# Drone_esp32-S3.net
KiCad netlist of a schematic drawn in Altium Designer
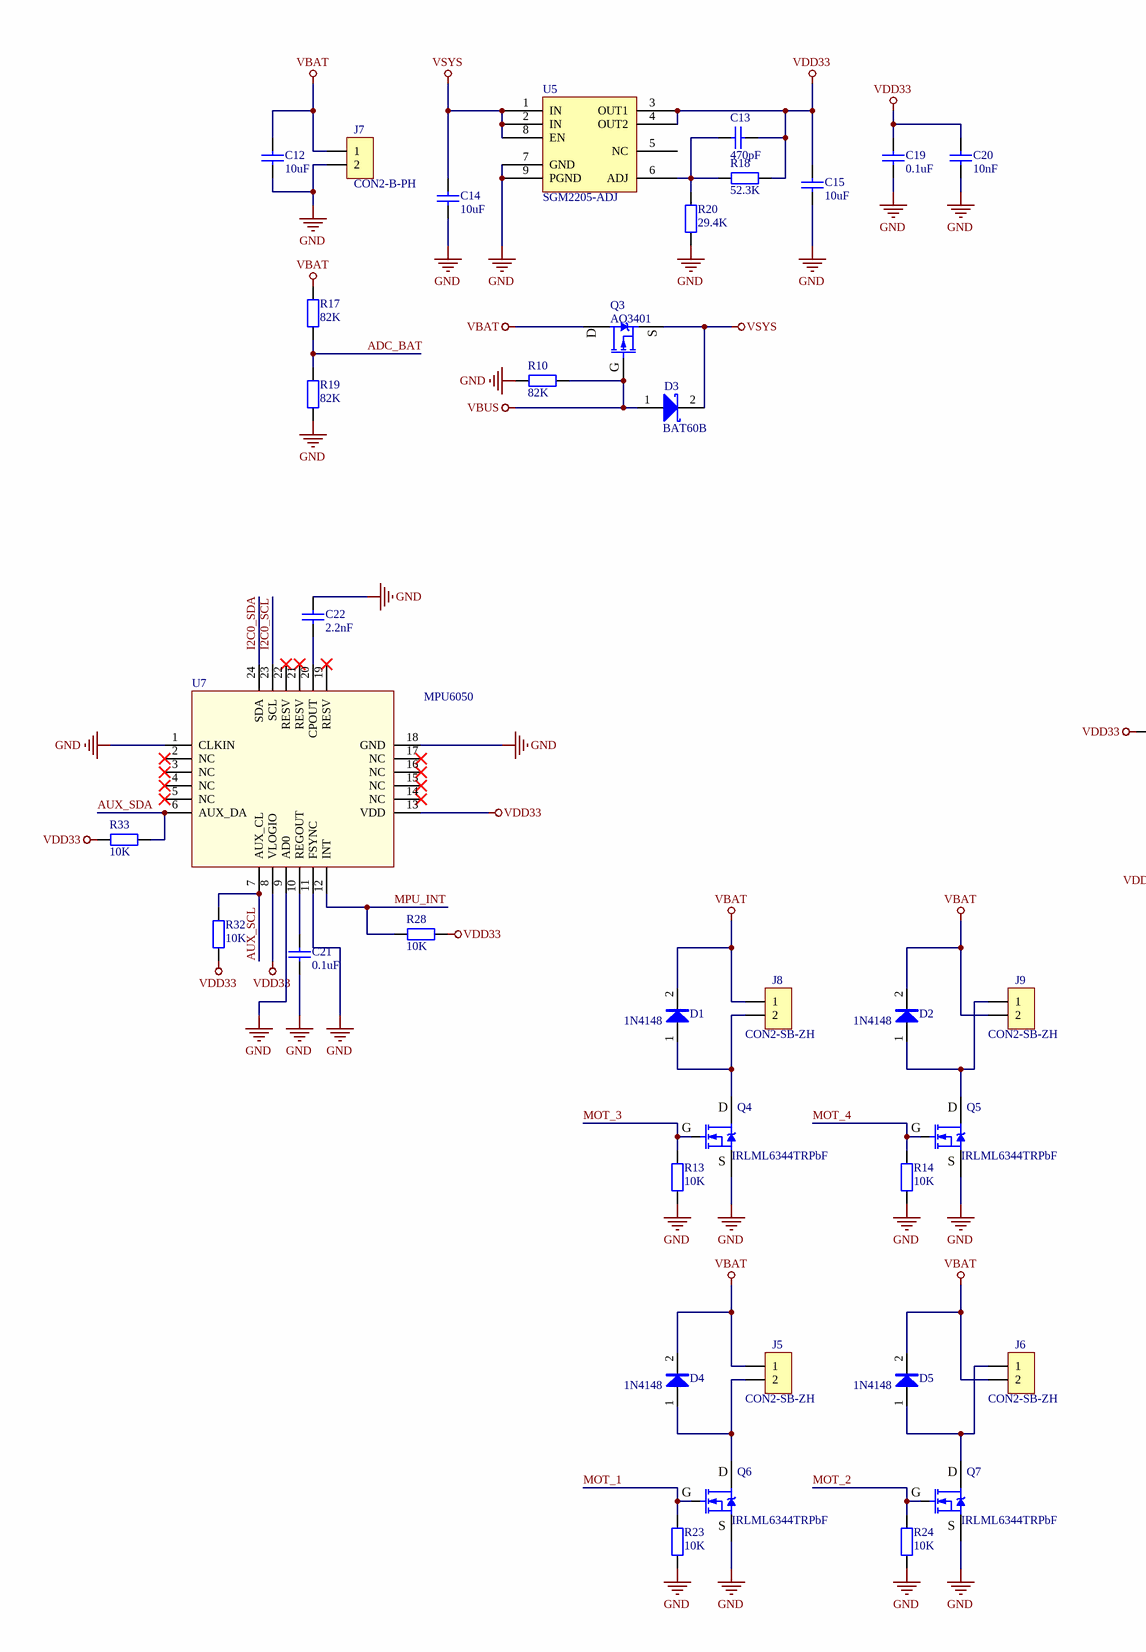
[diagram p0: Drone_esp32-S3.SchDoc, left]
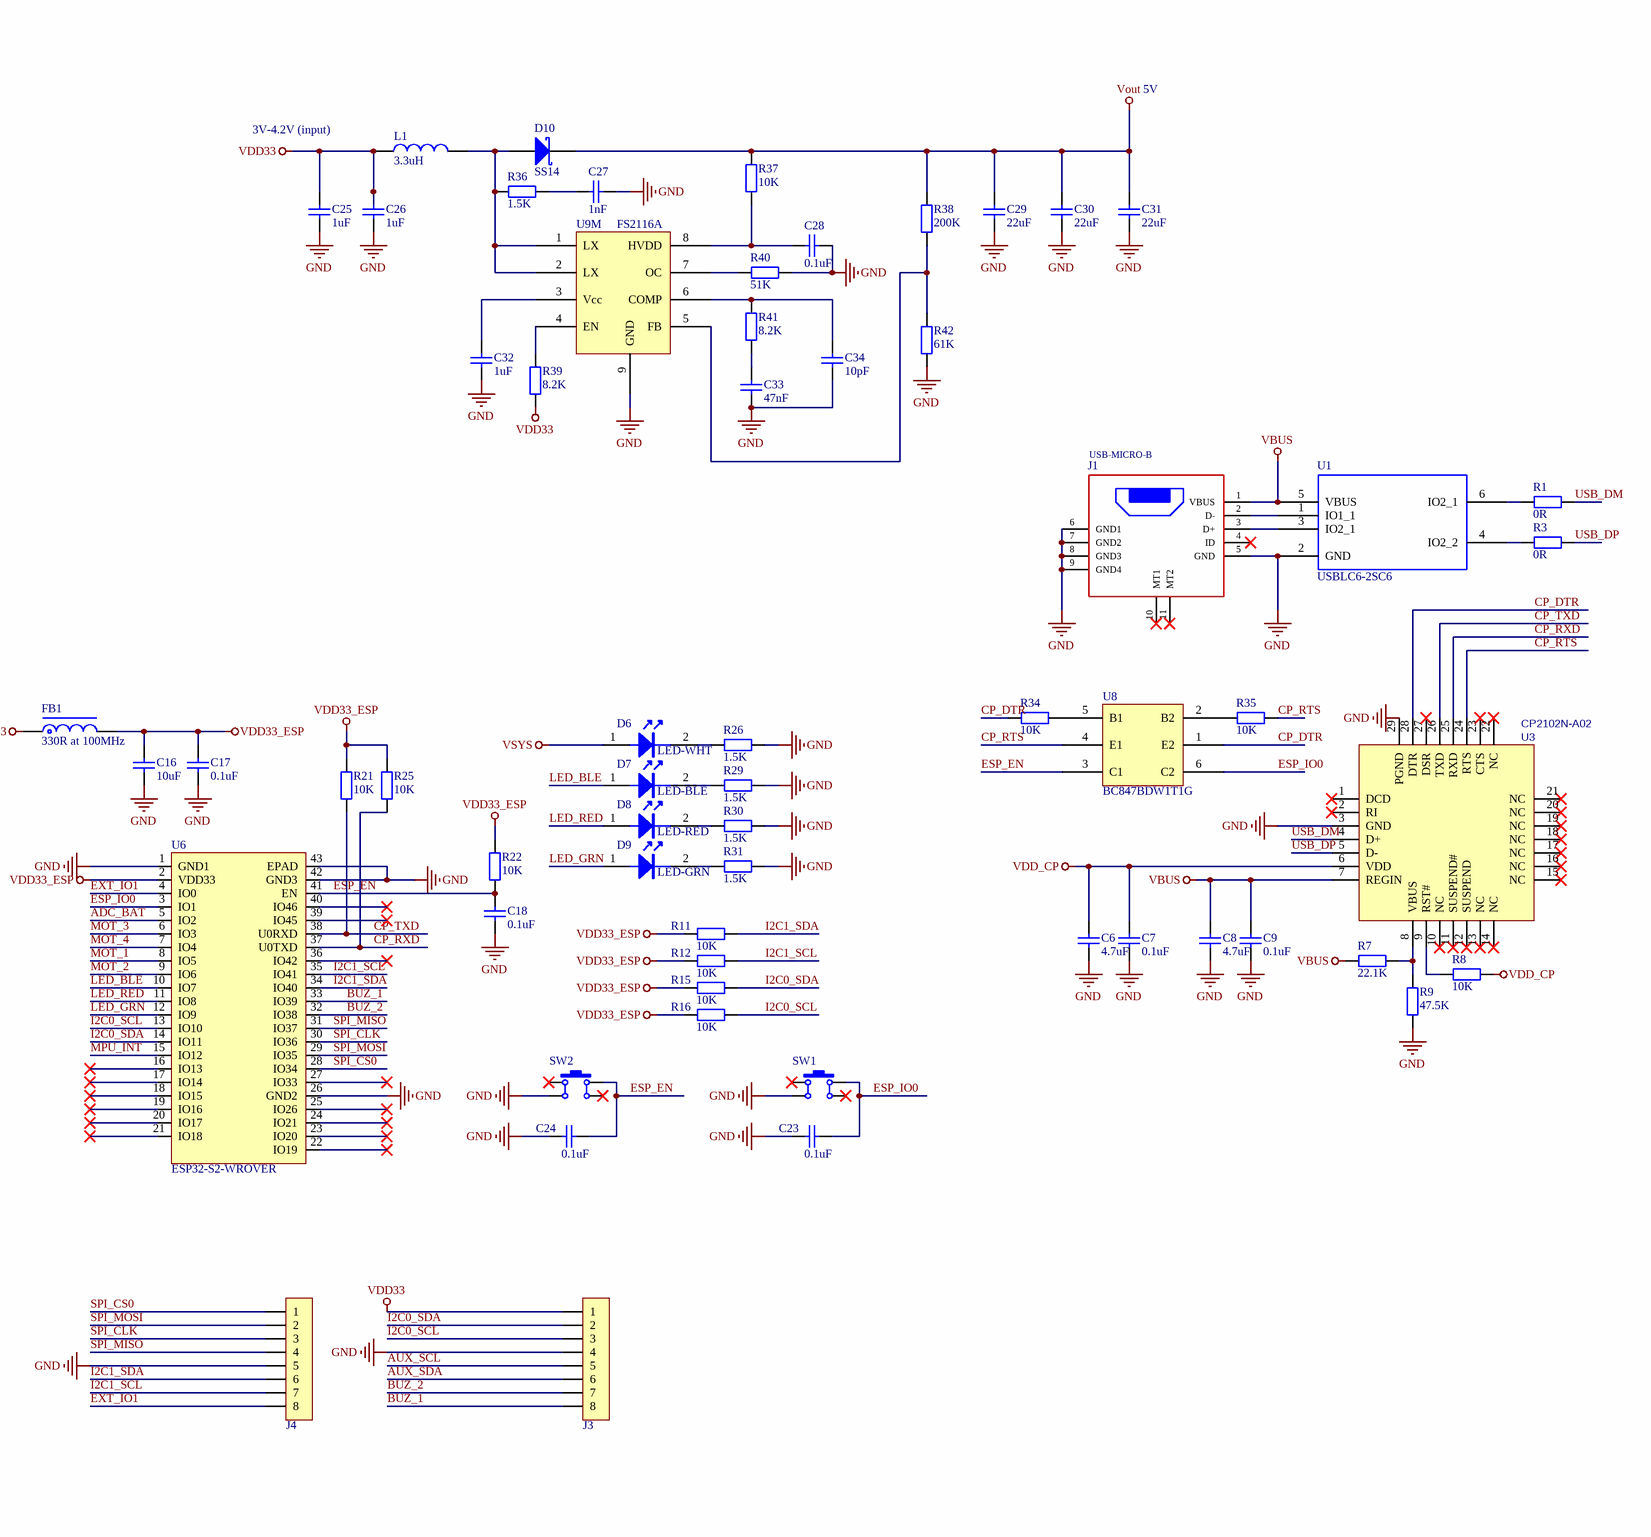
[diagram p1: Drone_esp32-S3.SchDoc, right]

(export (version "E")
  (design (tool "Eeschema 10.0.6"))
  (components
    (comp (ref "C6")
      (value "4.7uF")
      (footprint "C0603_L")
      (description "贴片电容/MLCC电容")
      (libsource (lib "0.1 - 电阻-电容-电感-保险丝-晶振-晶体-磁珠-电位器-法拉电容-馈通电容") (part "C"))
    )
    (comp (ref "C7")
      (value "0.1uF")
      (footprint "C0402_L")
      (description "贴片电容/MLCC电容")
      (libsource (lib "0.1 - 电阻-电容-电感-保险丝-晶振-晶体-磁珠-电位器-法拉电容-馈通电容") (part "C"))
    )
    (comp (ref "C8")
      (value "4.7uF")
      (footprint "C0603_L")
      (description "贴片电容/MLCC电容")
      (libsource (lib "0.1 - 电阻-电容-电感-保险丝-晶振-晶体-磁珠-电位器-法拉电容-馈通电容") (part "C"))
    )
    (comp (ref "C9")
      (value "0.1uF")
      (footprint "C0402_L")
      (description "贴片电容/MLCC电容")
      (libsource (lib "0.1 - 电阻-电容-电感-保险丝-晶振-晶体-磁珠-电位器-法拉电容-馈通电容") (part "C"))
    )
    (comp (ref "C12")
      (value "10uF")
      (footprint "C0603_L")
      (description "贴片电容/MLCC电容")
      (libsource (lib "0.1 - 电阻-电容-电感-保险丝-晶振-晶体-磁珠-电位器-法拉电容-馈通电容") (part "C"))
    )
    (comp (ref "C13")
      (value "470pF")
      (footprint "C0402_L")
      (description "贴片电容/MLCC电容")
      (libsource (lib "0.1 - 电阻-电容-电感-保险丝-晶振-晶体-磁珠-电位器-法拉电容-馈通电容") (part "C"))
    )
    (comp (ref "C14")
      (value "10uF")
      (footprint "C0603_L")
      (description "贴片电容/MLCC电容")
      (libsource (lib "0.1 - 电阻-电容-电感-保险丝-晶振-晶体-磁珠-电位器-法拉电容-馈通电容") (part "C"))
    )
    (comp (ref "C15")
      (value "10uF")
      (footprint "C0603_L")
      (description "贴片电容/MLCC电容")
      (libsource (lib "0.1 - 电阻-电容-电感-保险丝-晶振-晶体-磁珠-电位器-法拉电容-馈通电容") (part "C"))
    )
    (comp (ref "C16")
      (value "10uF")
      (footprint "C0603_L")
      (description "贴片电容/MLCC电容")
      (libsource (lib "0.1 - 电阻-电容-电感-保险丝-晶振-晶体-磁珠-电位器-法拉电容-馈通电容") (part "C"))
    )
    (comp (ref "C17")
      (value "0.1uF")
      (footprint "C0402_L")
      (description "贴片电容/MLCC电容")
      (libsource (lib "0.1 - 电阻-电容-电感-保险丝-晶振-晶体-磁珠-电位器-法拉电容-馈通电容") (part "C"))
    )
    (comp (ref "C18")
      (value "0.1uF")
      (footprint "C0402_L")
      (description "贴片电容/MLCC电容")
      (libsource (lib "0.1 - 电阻-电容-电感-保险丝-晶振-晶体-磁珠-电位器-法拉电容-馈通电容") (part "C"))
    )
    (comp (ref "C19")
      (value "0.1uF")
      (footprint "C0402_L")
      (description "贴片电容/MLCC电容")
      (libsource (lib "0.1 - 电阻-电容-电感-保险丝-晶振-晶体-磁珠-电位器-法拉电容-馈通电容") (part "C"))
    )
    (comp (ref "C20")
      (value "10nF")
      (footprint "C0402_L")
      (description "贴片电容/MLCC电容")
      (libsource (lib "0.1 - 电阻-电容-电感-保险丝-晶振-晶体-磁珠-电位器-法拉电容-馈通电容") (part "C"))
    )
    (comp (ref "C21")
      (value "0.1uF")
      (footprint "C0402_L")
      (description "贴片电容/MLCC电容")
      (libsource (lib "0.1 - 电阻-电容-电感-保险丝-晶振-晶体-磁珠-电位器-法拉电容-馈通电容") (part "C"))
    )
    (comp (ref "C22")
      (value "2.2nF")
      (footprint "C0402_L")
      (description "贴片电容/MLCC电容")
      (libsource (lib "0.1 - 电阻-电容-电感-保险丝-晶振-晶体-磁珠-电位器-法拉电容-馈通电容") (part "C"))
    )
    (comp (ref "C23")
      (value "0.1uF")
      (footprint "C0402_L")
      (description "贴片电容/MLCC电容")
      (libsource (lib "0.1 - 电阻-电容-电感-保险丝-晶振-晶体-磁珠-电位器-法拉电容-馈通电容") (part "C"))
    )
    (comp (ref "C24")
      (value "0.1uF")
      (footprint "C0402_L")
      (description "贴片电容/MLCC电容")
      (libsource (lib "0.1 - 电阻-电容-电感-保险丝-晶振-晶体-磁珠-电位器-法拉电容-馈通电容") (part "C"))
    )
    (comp (ref "C25")
      (value "1uF")
      (footprint "C0603_L")
      (description "贴片电容/MLCC电容")
      (libsource (lib "0.1 - 电阻-电容-电感-保险丝-晶振-晶体-磁珠-电位器-法拉电容-馈通电容") (part "C"))
    )
    (comp (ref "C26")
      (value "1uF")
      (footprint "C0603_L")
      (description "贴片电容/MLCC电容")
      (libsource (lib "0.1 - 电阻-电容-电感-保险丝-晶振-晶体-磁珠-电位器-法拉电容-馈通电容") (part "C"))
    )
    (comp (ref "C27")
      (value "1nF")
      (footprint "C0603_L")
      (description "贴片电容/MLCC电容")
      (libsource (lib "0.1 - 电阻-电容-电感-保险丝-晶振-晶体-磁珠-电位器-法拉电容-馈通电容") (part "C"))
    )
    (comp (ref "C28")
      (value "0.1uF")
      (footprint "C0402_L")
      (description "贴片电容/MLCC电容")
      (libsource (lib "0.1 - 电阻-电容-电感-保险丝-晶振-晶体-磁珠-电位器-法拉电容-馈通电容") (part "C"))
    )
    (comp (ref "C29")
      (value "22uF")
      (footprint "C0603_L")
      (description "贴片电容/MLCC电容")
      (libsource (lib "0.1 - 电阻-电容-电感-保险丝-晶振-晶体-磁珠-电位器-法拉电容-馈通电容") (part "C"))
    )
    (comp (ref "C30")
      (value "22uF")
      (footprint "C0603_L")
      (description "贴片电容/MLCC电容")
      (libsource (lib "0.1 - 电阻-电容-电感-保险丝-晶振-晶体-磁珠-电位器-法拉电容-馈通电容") (part "C"))
    )
    (comp (ref "C31")
      (value "22uF")
      (footprint "C0603_L")
      (description "贴片电容/MLCC电容")
      (libsource (lib "0.1 - 电阻-电容-电感-保险丝-晶振-晶体-磁珠-电位器-法拉电容-馈通电容") (part "C"))
    )
    (comp (ref "C32")
      (value "1uF")
      (footprint "C0402_L")
      (description "贴片电容/MLCC电容")
      (libsource (lib "0.1 - 电阻-电容-电感-保险丝-晶振-晶体-磁珠-电位器-法拉电容-馈通电容") (part "C"))
    )
    (comp (ref "C33")
      (value "47nF")
      (footprint "C0603_L")
      (description "贴片电容/MLCC电容")
      (libsource (lib "0.1 - 电阻-电容-电感-保险丝-晶振-晶体-磁珠-电位器-法拉电容-馈通电容") (part "C"))
    )
    (comp (ref "C34")
      (value "10pF")
      (footprint "C0402_L")
      (description "贴片电容/MLCC电容")
      (libsource (lib "0.1 - 电阻-电容-电感-保险丝-晶振-晶体-磁珠-电位器-法拉电容-馈通电容") (part "C"))
    )
    (comp (ref "D1")
      (value "1N4148")
      (footprint "SOD-523")
      (description "开关二极管")
      (libsource (lib "0.2 - 二极管-TVS-ESD-整流桥-放电管") (part "1N4148"))
    )
    (comp (ref "D2")
      (value "1N4148")
      (footprint "SOD-523")
      (description "开关二极管")
      (libsource (lib "0.2 - 二极管-TVS-ESD-整流桥-放电管") (part "1N4148"))
    )
    (comp (ref "D3")
      (value "BAT60B")
      (footprint "SOD-323")
      (description "肖特基二极管")
      (libsource (lib "0.2 - 二极管-TVS-ESD-整流桥-放电管") (part "D-Schottky"))
    )
    (comp (ref "D4")
      (value "1N4148")
      (footprint "SOD-523")
      (description "开关二极管")
      (libsource (lib "0.2 - 二极管-TVS-ESD-整流桥-放电管") (part "1N4148"))
    )
    (comp (ref "D5")
      (value "1N4148")
      (footprint "SOD-523")
      (description "开关二极管")
      (libsource (lib "0.2 - 二极管-TVS-ESD-整流桥-放电管") (part "1N4148"))
    )
    (comp (ref "D6")
      (value "LED-WHT")
      (footprint "LED3010-S")
      (description "LED")
      (libsource (lib "0.2 - 二极管-TVS-ESD-整流桥-放电管") (part "发光二极管"))
    )
    (comp (ref "D7")
      (value "LED-BLE")
      (footprint "LED3010-S")
      (description "LED")
      (libsource (lib "0.2 - 二极管-TVS-ESD-整流桥-放电管") (part "发光二极管"))
    )
    (comp (ref "D8")
      (value "LED-RED")
      (footprint "LED3010-S")
      (description "LED")
      (libsource (lib "0.2 - 二极管-TVS-ESD-整流桥-放电管") (part "发光二极管"))
    )
    (comp (ref "D9")
      (value "LED-GRN")
      (footprint "LED3010-S")
      (description "LED")
      (libsource (lib "0.2 - 二极管-TVS-ESD-整流桥-放电管") (part "发光二极管"))
    )
    (comp (ref "D10")
      (value "SS14")
      (footprint "SMA")
      (description "肖特基二极管")
      (libsource (lib "0.2 - 二极管-TVS-ESD-整流桥-放电管") (part "SS14"))
    )
    (comp (ref "FB1")
      (value "330R at 100MHz")
      (footprint "L0603")
      (description "贴片磁珠")
      (libsource (lib "0.1 - 电阻-电容-电感-保险丝-晶振-晶体-磁珠-电位器-法拉电容-馈通电容") (part "FB"))
    )
    (comp (ref "J1")
      (value "USB-MICRO-B")
      (footprint "USB2.0_MICRO-B_5")
      (description "USB3.1_Micro-B母座")
      (libsource (lib "0.6 - 电源_音频_USB Type-C_HDMI_XT60_5557_D-SUB_RJ45_SD-TF_SIM插座") (part "USB3.1_Micro-B"))
    )
    (comp (ref "J3")
      (value "HDR-1X8")
      (footprint "A2005HWV-S-XP-A")
      (description "8P接插件")
      (libsource (lib "5.4 - 2.0mm连接器(PHB2.0_PHD2.0_2.0排针排母)") (part "Header 8"))
    )
    (comp (ref "J4")
      (value "HDR-1X8")
      (footprint "A2005HWV-S-XP-A")
      (description "8P接插件")
      (libsource (lib "5.4 - 2.0mm连接器(PHB2.0_PHD2.0_2.0排针排母)") (part "Header 8"))
    )
    (comp (ref "J5")
      (value "CON2-SB-ZH")
      (footprint "CON2X1_1P5_SMT_ZH-2A_DIP")
      (description "2P接插件")
      (libsource (lib "5.4 - 2.0mm连接器(PHB2.0_PHD2.0_2.0排针排母)") (part "Header 2"))
    )
    (comp (ref "J6")
      (value "CON2-SB-ZH")
      (footprint "CON2X1_1P5_SMT_ZH-2A_DIP")
      (description "2P接插件")
      (libsource (lib "5.4 - 2.0mm连接器(PHB2.0_PHD2.0_2.0排针排母)") (part "Header 2"))
    )
    (comp (ref "J7")
      (value "CON2-B-PH")
      (footprint "CON2X1")
      (description "2P接插件")
      (libsource (lib "5.4 - 2.0mm连接器(PHB2.0_PHD2.0_2.0排针排母)") (part "Header 2"))
    )
    (comp (ref "J8")
      (value "CON2-SB-ZH")
      (footprint "CON2X1_1P5_SMT_ZH-2A_DIP")
      (description "2P接插件")
      (libsource (lib "5.4 - 2.0mm连接器(PHB2.0_PHD2.0_2.0排针排母)") (part "Header 2"))
    )
    (comp (ref "J9")
      (value "CON2-SB-ZH")
      (footprint "CON2X1_1P5_SMT_ZH-2A_DIP")
      (description "2P接插件")
      (libsource (lib "5.4 - 2.0mm连接器(PHB2.0_PHD2.0_2.0排针排母)") (part "Header 2"))
    )
    (comp (ref "L1")
      (value "3.3uH")
      (footprint "L0805")
      (description "贴片小功率电感")
      (libsource (lib "0.1 - 电阻-电容-电感-保险丝-晶振-晶体-磁珠-电位器-法拉电容-馈通电容") (part "L"))
    )
    (comp (ref "Q3")
      (value "AO3401")
      (footprint "SOT-23-3")
      (description "P沟道 30V/4.2A")
      (libsource (lib "0.4 - 三极管-场效应管-可控硅") (part "AO3401"))
    )
    (comp (ref "Q4")
      (value "IRLML6344TRPbF")
      (footprint "SOT-23-3")
      (libsource (lib "0.4 - 三极管-场效应管-可控硅") (part "SI2302"))
    )
    (comp (ref "Q5")
      (value "IRLML6344TRPbF")
      (footprint "SOT-23-3")
      (libsource (lib "0.4 - 三极管-场效应管-可控硅") (part "SI2302"))
    )
    (comp (ref "Q6")
      (value "IRLML6344TRPbF")
      (footprint "SOT-23-3")
      (libsource (lib "0.4 - 三极管-场效应管-可控硅") (part "SI2302"))
    )
    (comp (ref "Q7")
      (value "IRLML6344TRPbF")
      (footprint "SOT-23-3")
      (libsource (lib "0.4 - 三极管-场效应管-可控硅") (part "SI2302"))
    )
    (comp (ref "R1")
      (value "0R")
      (footprint "R0402_M")
      (description "贴片电阻")
      (libsource (lib "0.1 - 电阻-电容-电感-保险丝-晶振-晶体-磁珠-电位器-法拉电容-馈通电容") (part "R"))
    )
    (comp (ref "R3")
      (value "0R")
      (footprint "R0402_M")
      (description "贴片电阻")
      (libsource (lib "0.1 - 电阻-电容-电感-保险丝-晶振-晶体-磁珠-电位器-法拉电容-馈通电容") (part "R"))
    )
    (comp (ref "R7")
      (value "22.1K")
      (footprint "R0402_M")
      (description "贴片电阻")
      (libsource (lib "0.1 - 电阻-电容-电感-保险丝-晶振-晶体-磁珠-电位器-法拉电容-馈通电容") (part "R"))
    )
    (comp (ref "R8")
      (value "10K")
      (footprint "R0402_M")
      (description "贴片电阻")
      (libsource (lib "0.1 - 电阻-电容-电感-保险丝-晶振-晶体-磁珠-电位器-法拉电容-馈通电容") (part "R"))
    )
    (comp (ref "R9")
      (value "47.5K")
      (footprint "R0402_M")
      (description "贴片电阻")
      (libsource (lib "0.1 - 电阻-电容-电感-保险丝-晶振-晶体-磁珠-电位器-法拉电容-馈通电容") (part "R"))
    )
    (comp (ref "R10")
      (value "82K")
      (footprint "R0402_M")
      (description "贴片电阻")
      (libsource (lib "0.1 - 电阻-电容-电感-保险丝-晶振-晶体-磁珠-电位器-法拉电容-馈通电容") (part "R"))
    )
    (comp (ref "R11")
      (value "10K")
      (footprint "R0402_M")
      (description "贴片电阻")
      (libsource (lib "0.1 - 电阻-电容-电感-保险丝-晶振-晶体-磁珠-电位器-法拉电容-馈通电容") (part "R"))
    )
    (comp (ref "R12")
      (value "10K")
      (footprint "R0402_M")
      (description "贴片电阻")
      (libsource (lib "0.1 - 电阻-电容-电感-保险丝-晶振-晶体-磁珠-电位器-法拉电容-馈通电容") (part "R"))
    )
    (comp (ref "R13")
      (value "10K")
      (footprint "R0402_M")
      (description "贴片电阻")
      (libsource (lib "0.1 - 电阻-电容-电感-保险丝-晶振-晶体-磁珠-电位器-法拉电容-馈通电容") (part "R"))
    )
    (comp (ref "R14")
      (value "10K")
      (footprint "R0402_M")
      (description "贴片电阻")
      (libsource (lib "0.1 - 电阻-电容-电感-保险丝-晶振-晶体-磁珠-电位器-法拉电容-馈通电容") (part "R"))
    )
    (comp (ref "R15")
      (value "10K")
      (footprint "R0402_M")
      (description "贴片电阻")
      (libsource (lib "0.1 - 电阻-电容-电感-保险丝-晶振-晶体-磁珠-电位器-法拉电容-馈通电容") (part "R"))
    )
    (comp (ref "R16")
      (value "10K")
      (footprint "R0402_M")
      (description "贴片电阻")
      (libsource (lib "0.1 - 电阻-电容-电感-保险丝-晶振-晶体-磁珠-电位器-法拉电容-馈通电容") (part "R"))
    )
    (comp (ref "R17")
      (value "82K")
      (footprint "R0402_M")
      (description "贴片电阻")
      (libsource (lib "0.1 - 电阻-电容-电感-保险丝-晶振-晶体-磁珠-电位器-法拉电容-馈通电容") (part "R"))
    )
    (comp (ref "R18")
      (value "52.3K")
      (footprint "R0402_M")
      (description "贴片电阻")
      (libsource (lib "0.1 - 电阻-电容-电感-保险丝-晶振-晶体-磁珠-电位器-法拉电容-馈通电容") (part "R"))
    )
    (comp (ref "R19")
      (value "82K")
      (footprint "R0402_M")
      (description "贴片电阻")
      (libsource (lib "0.1 - 电阻-电容-电感-保险丝-晶振-晶体-磁珠-电位器-法拉电容-馈通电容") (part "R"))
    )
    (comp (ref "R20")
      (value "29.4K")
      (footprint "R0402_M")
      (description "贴片电阻")
      (libsource (lib "0.1 - 电阻-电容-电感-保险丝-晶振-晶体-磁珠-电位器-法拉电容-馈通电容") (part "R"))
    )
    (comp (ref "R21")
      (value "10K")
      (footprint "R0402_M")
      (description "贴片电阻")
      (libsource (lib "0.1 - 电阻-电容-电感-保险丝-晶振-晶体-磁珠-电位器-法拉电容-馈通电容") (part "R"))
    )
    (comp (ref "R22")
      (value "10K")
      (footprint "R0402_M")
      (description "贴片电阻")
      (libsource (lib "0.1 - 电阻-电容-电感-保险丝-晶振-晶体-磁珠-电位器-法拉电容-馈通电容") (part "R"))
    )
    (comp (ref "R23")
      (value "10K")
      (footprint "R0402_M")
      (description "贴片电阻")
      (libsource (lib "0.1 - 电阻-电容-电感-保险丝-晶振-晶体-磁珠-电位器-法拉电容-馈通电容") (part "R"))
    )
    (comp (ref "R24")
      (value "10K")
      (footprint "R0402_M")
      (description "贴片电阻")
      (libsource (lib "0.1 - 电阻-电容-电感-保险丝-晶振-晶体-磁珠-电位器-法拉电容-馈通电容") (part "R"))
    )
    (comp (ref "R25")
      (value "10K")
      (footprint "R0402_M")
      (description "贴片电阻")
      (libsource (lib "0.1 - 电阻-电容-电感-保险丝-晶振-晶体-磁珠-电位器-法拉电容-馈通电容") (part "R"))
    )
    (comp (ref "R26")
      (value "1.5K")
      (footprint "R0402_M")
      (description "贴片电阻")
      (libsource (lib "0.1 - 电阻-电容-电感-保险丝-晶振-晶体-磁珠-电位器-法拉电容-馈通电容") (part "R"))
    )
    (comp (ref "R28")
      (value "10K")
      (footprint "R0402_M")
      (description "贴片电阻")
      (libsource (lib "0.1 - 电阻-电容-电感-保险丝-晶振-晶体-磁珠-电位器-法拉电容-馈通电容") (part "R"))
    )
    (comp (ref "R29")
      (value "1.5K")
      (footprint "R0402_M")
      (description "贴片电阻")
      (libsource (lib "0.1 - 电阻-电容-电感-保险丝-晶振-晶体-磁珠-电位器-法拉电容-馈通电容") (part "R"))
    )
    (comp (ref "R30")
      (value "1.5K")
      (footprint "R0402_M")
      (description "贴片电阻")
      (libsource (lib "0.1 - 电阻-电容-电感-保险丝-晶振-晶体-磁珠-电位器-法拉电容-馈通电容") (part "R"))
    )
    (comp (ref "R31")
      (value "1.5K")
      (footprint "R0402_M")
      (description "贴片电阻")
      (libsource (lib "0.1 - 电阻-电容-电感-保险丝-晶振-晶体-磁珠-电位器-法拉电容-馈通电容") (part "R"))
    )
    (comp (ref "R32")
      (value "10K")
      (footprint "R0402_M")
      (description "贴片电阻")
      (libsource (lib "0.1 - 电阻-电容-电感-保险丝-晶振-晶体-磁珠-电位器-法拉电容-馈通电容") (part "R"))
    )
    (comp (ref "R33")
      (value "10K")
      (footprint "R0402_M")
      (description "贴片电阻")
      (libsource (lib "0.1 - 电阻-电容-电感-保险丝-晶振-晶体-磁珠-电位器-法拉电容-馈通电容") (part "R"))
    )
    (comp (ref "R34")
      (value "10K")
      (footprint "R0402_M")
      (description "贴片电阻")
      (libsource (lib "0.1 - 电阻-电容-电感-保险丝-晶振-晶体-磁珠-电位器-法拉电容-馈通电容") (part "R"))
    )
    (comp (ref "R35")
      (value "10K")
      (footprint "R0402_M")
      (description "贴片电阻")
      (libsource (lib "0.1 - 电阻-电容-电感-保险丝-晶振-晶体-磁珠-电位器-法拉电容-馈通电容") (part "R"))
    )
    (comp (ref "R36")
      (value "1.5K")
      (footprint "R0402_M")
      (description "贴片电阻")
      (libsource (lib "0.1 - 电阻-电容-电感-保险丝-晶振-晶体-磁珠-电位器-法拉电容-馈通电容") (part "R"))
    )
    (comp (ref "R37")
      (value "10K")
      (footprint "R0402_M")
      (description "贴片电阻")
      (libsource (lib "0.1 - 电阻-电容-电感-保险丝-晶振-晶体-磁珠-电位器-法拉电容-馈通电容") (part "R"))
    )
    (comp (ref "R38")
      (value "200K")
      (footprint "R0402_M")
      (description "贴片电阻")
      (libsource (lib "0.1 - 电阻-电容-电感-保险丝-晶振-晶体-磁珠-电位器-法拉电容-馈通电容") (part "R"))
    )
    (comp (ref "R39")
      (value "8.2K")
      (footprint "R0402_M")
      (description "贴片电阻")
      (libsource (lib "0.1 - 电阻-电容-电感-保险丝-晶振-晶体-磁珠-电位器-法拉电容-馈通电容") (part "R"))
    )
    (comp (ref "R40")
      (value "51K")
      (footprint "R0402_M")
      (description "贴片电阻")
      (libsource (lib "0.1 - 电阻-电容-电感-保险丝-晶振-晶体-磁珠-电位器-法拉电容-馈通电容") (part "R"))
    )
    (comp (ref "R41")
      (value "8.2K")
      (footprint "R0402_M")
      (description "贴片电阻")
      (libsource (lib "0.1 - 电阻-电容-电感-保险丝-晶振-晶体-磁珠-电位器-法拉电容-馈通电容") (part "R"))
    )
    (comp (ref "R42")
      (value "61K")
      (footprint "R0402_M")
      (description "贴片电阻")
      (libsource (lib "0.1 - 电阻-电容-电感-保险丝-晶振-晶体-磁珠-电位器-法拉电容-馈通电容") (part "R"))
    )
    (comp (ref "SW1")
      (value "6x6x5")
      (footprint "SW-SMD-3.5*3.0_4P")
      (description "4脚微动开关")
      (libsource (lib "0.5 - 按键_开关_蜂鸣器_电池_测试点_Mark点_铜柱") (part "SW-PB4"))
    )
    (comp (ref "SW2")
      (value "6x6x5")
      (footprint "SW-SMD-3.5*3.0_4P")
      (description "4脚微动开关")
      (libsource (lib "0.5 - 按键_开关_蜂鸣器_电池_测试点_Mark点_铜柱") (part "SW-PB4"))
    )
    (comp (ref "U1")
      (value "USBLC6-2SC6")
      (footprint "USBLC6-2SC6")
      (libsource (lib "USBLC6-2SC6") (part "USBLC6-2SC6"))
    )
    (comp (ref "U3")
      (value "CP2102N-A02")
      (footprint "FP-CP2102N-A02-GQFN28-MFG")
      (description "USB转UART 桥接控制器")
      (libsource (lib "0.8 - 常见芯片") (part "CP2102-GMR"))
    )
    (comp (ref "U5")
      (value "SGM2205-ADJ")
      (footprint "SMG2205-ADJ")
      (description "Vout=1.2(1+Ra/Rb)=3.3V")
      (libsource (lib "Schlib1") (part "SGM2205-ADJ"))
    )
    (comp (ref "U6")
      (value "ESP32-S2-WROVER")
      (footprint "ESP32-S2-WROVER")
      (libsource (lib "ESP32-S2-WROVER") (part "ESP32-S2"))
    )
    (comp (ref "U7")
      (value "MPU6050")
      (footprint "QFN24 4x4_L")
      (description "三轴加速度+三轴陀螺仪")
      (libsource (lib "0.9 - 传感器-存储器-模块") (part "MPU6050"))
    )
    (comp (ref "U8")
      (value "BC847BDW1T1G")
      (footprint "ONSC-SOT-363-6-419B-02_W_V")
      (description "ON Semi BC847BDW1T1G Dual NPN Bipolar Transistor; 0.1 A; 45 V; 6-Pin SC-88")
      (libsource (lib "Hongyu Yang") (part "BC847BDW1T1G"))
    )
    (comp (ref "U9")
      (value "FS2116A")
      (footprint "PCBComponent_1")
      (libsource (lib "FS2116A") (part "FS2116A"))
    )
  )
  (nets
    (net (code "1") (name "/ADC_BAT") (class "Default")
      (node (ref "R17") (pin "1") (pinfunction "1_1") (pintype "passive"))
      (node (ref "R19") (pin "2") (pinfunction "2_2") (pintype "passive"))
      (node (ref "U6") (pin "5") (pinfunction "IO2_5") (pintype "passive"))
    )
    (net (code "2") (name "/AUX_SCL") (class "Default")
      (node (ref "J3") (pin "5") (pinfunction "5_5") (pintype "passive"))
      (node (ref "R32") (pin "2") (pinfunction "2_2") (pintype "passive"))
      (node (ref "U7") (pin "7") (pinfunction "AUX_CL_7") (pintype "passive"))
    )
    (net (code "3") (name "/AUX_SDA") (class "Default")
      (node (ref "J3") (pin "6") (pinfunction "6_6") (pintype "passive"))
      (node (ref "R33") (pin "2") (pinfunction "2_2") (pintype "passive"))
      (node (ref "U7") (pin "6") (pinfunction "AUX_DA_6") (pintype "passive"))
    )
    (net (code "4") (name "/BUZ_1") (class "Default")
      (node (ref "J3") (pin "8") (pinfunction "8_8") (pintype "passive"))
      (node (ref "U6") (pin "33") (pinfunction "IO39_33") (pintype "passive"))
    )
    (net (code "5") (name "/BUZ_2") (class "Default")
      (node (ref "J3") (pin "7") (pinfunction "7_7") (pintype "passive"))
      (node (ref "U6") (pin "32") (pinfunction "IO38_32") (pintype "passive"))
    )
    (net (code "6") (name "/CP_DTR") (class "Default")
      (node (ref "R34") (pin "1") (pinfunction "1_1") (pintype "passive"))
      (node (ref "U3") (pin "28") (pinfunction "DTR_28") (pintype "passive"))
      (node (ref "U8") (pin "1") (pinfunction "E2_1") (pintype "passive"))
    )
    (net (code "7") (name "/CP_RTS") (class "Default")
      (node (ref "R35") (pin "2") (pinfunction "2_2") (pintype "passive"))
      (node (ref "U3") (pin "24") (pinfunction "RTS_24") (pintype "passive"))
      (node (ref "U8") (pin "4") (pinfunction "E1_4") (pintype "passive"))
    )
    (net (code "8") (name "/CP_RXD") (class "Default")
      (node (ref "R25") (pin "1") (pinfunction "1_1") (pintype "passive"))
      (node (ref "U3") (pin "25") (pinfunction "RXD_25") (pintype "passive"))
      (node (ref "U6") (pin "37") (pinfunction "U0TXD_37") (pintype "passive"))
    )
    (net (code "9") (name "/CP_TXD") (class "Default")
      (node (ref "R21") (pin "1") (pinfunction "1_1") (pintype "passive"))
      (node (ref "U3") (pin "26") (pinfunction "TXD_26") (pintype "passive"))
      (node (ref "U6") (pin "38") (pinfunction "U0RXD_38") (pintype "passive"))
    )
    (net (code "10") (name "/ESP_EN") (class "Default")
      (node (ref "C18") (pin "2") (pinfunction "2_2") (pintype "passive"))
      (node (ref "C24") (pin "2") (pinfunction "2_2") (pintype "passive"))
      (node (ref "R22") (pin "1") (pinfunction "1_1") (pintype "passive"))
      (node (ref "SW2") (pin "2") (pinfunction "2_2") (pintype "passive"))
      (node (ref "U6") (pin "41") (pinfunction "EN_41") (pintype "passive"))
      (node (ref "U8") (pin "3") (pinfunction "C1_3") (pintype "passive"))
    )
    (net (code "11") (name "/ESP_IO0") (class "Default")
      (node (ref "C23") (pin "2") (pinfunction "2_2") (pintype "passive"))
      (node (ref "SW1") (pin "2") (pinfunction "2_2") (pintype "passive"))
      (node (ref "U6") (pin "3") (pinfunction "IO1_3") (pintype "passive"))
      (node (ref "U8") (pin "6") (pinfunction "C2_6") (pintype "passive"))
    )
    (net (code "12") (name "/EXT_IO1") (class "Default")
      (node (ref "J4") (pin "8") (pinfunction "8_8") (pintype "passive"))
      (node (ref "U6") (pin "4") (pinfunction "IO0_4") (pintype "passive"))
    )
    (net (code "13") (name "/I2C0_SCL") (class "Default")
      (node (ref "J3") (pin "3") (pinfunction "3_3") (pintype "passive"))
      (node (ref "R16") (pin "2") (pinfunction "2_2") (pintype "passive"))
      (node (ref "U6") (pin "13") (pinfunction "IO10_13") (pintype "passive"))
      (node (ref "U7") (pin "23") (pinfunction "SCL_23") (pintype "passive"))
    )
    (net (code "14") (name "/I2C0_SDA") (class "Default")
      (node (ref "J3") (pin "2") (pinfunction "2_2") (pintype "passive"))
      (node (ref "R15") (pin "2") (pinfunction "2_2") (pintype "passive"))
      (node (ref "U6") (pin "14") (pinfunction "IO11_14") (pintype "passive"))
      (node (ref "U7") (pin "24") (pinfunction "SDA_24") (pintype "passive"))
    )
    (net (code "15") (name "/I2C1_SCL") (class "Default")
      (node (ref "J4") (pin "7") (pinfunction "7_7") (pintype "passive"))
      (node (ref "R12") (pin "2") (pinfunction "2_2") (pintype "passive"))
      (node (ref "U6") (pin "35") (pinfunction "IO41_35") (pintype "passive"))
    )
    (net (code "16") (name "/I2C1_SDA") (class "Default")
      (node (ref "J4") (pin "6") (pinfunction "6_6") (pintype "passive"))
      (node (ref "R11") (pin "2") (pinfunction "2_2") (pintype "passive"))
      (node (ref "U6") (pin "34") (pinfunction "IO40_34") (pintype "passive"))
    )
    (net (code "17") (name "/LED_BLE") (class "Default")
      (node (ref "D7") (pin "1") (pintype "passive"))
      (node (ref "U6") (pin "10") (pinfunction "IO7_10") (pintype "passive"))
    )
    (net (code "18") (name "/LED_GRN") (class "Default")
      (node (ref "D9") (pin "1") (pintype "passive"))
      (node (ref "U6") (pin "12") (pinfunction "IO9_12") (pintype "passive"))
    )
    (net (code "19") (name "/LED_RED") (class "Default")
      (node (ref "D8") (pin "1") (pintype "passive"))
      (node (ref "U6") (pin "11") (pinfunction "IO8_11") (pintype "passive"))
    )
    (net (code "20") (name "/MOT_1") (class "Default")
      (node (ref "Q6") (pin "1") (pinfunction "G_1") (pintype "passive"))
      (node (ref "R23") (pin "2") (pinfunction "2_2") (pintype "passive"))
      (node (ref "U6") (pin "8") (pinfunction "IO5_8") (pintype "passive"))
    )
    (net (code "21") (name "/MOT_2") (class "Default")
      (node (ref "Q7") (pin "1") (pinfunction "G_1") (pintype "passive"))
      (node (ref "R24") (pin "2") (pinfunction "2_2") (pintype "passive"))
      (node (ref "U6") (pin "9") (pinfunction "IO6_9") (pintype "passive"))
    )
    (net (code "22") (name "/MOT_3") (class "Default")
      (node (ref "Q4") (pin "1") (pinfunction "G_1") (pintype "passive"))
      (node (ref "R13") (pin "2") (pinfunction "2_2") (pintype "passive"))
      (node (ref "U6") (pin "6") (pinfunction "IO3_6") (pintype "passive"))
    )
    (net (code "23") (name "/MOT_4") (class "Default")
      (node (ref "Q5") (pin "1") (pinfunction "G_1") (pintype "passive"))
      (node (ref "R14") (pin "2") (pinfunction "2_2") (pintype "passive"))
      (node (ref "U6") (pin "7") (pinfunction "IO4_7") (pintype "passive"))
    )
    (net (code "24") (name "/MPU_INT") (class "Default")
      (node (ref "R28") (pin "1") (pinfunction "1_1") (pintype "passive"))
      (node (ref "U6") (pin "15") (pinfunction "IO12_15") (pintype "passive"))
      (node (ref "U7") (pin "12") (pinfunction "INT_12") (pintype "passive"))
    )
    (net (code "25") (name "/SPI_CLK") (class "Default")
      (node (ref "J4") (pin "3") (pinfunction "3_3") (pintype "passive"))
      (node (ref "U6") (pin "30") (pinfunction "IO36_30") (pintype "passive"))
    )
    (net (code "26") (name "/SPI_CS0") (class "Default")
      (node (ref "J4") (pin "1") (pinfunction "1_1") (pintype "passive"))
      (node (ref "U6") (pin "28") (pinfunction "IO34_28") (pintype "passive"))
    )
    (net (code "27") (name "/SPI_MISO") (class "Default")
      (node (ref "J4") (pin "4") (pinfunction "4_4") (pintype "passive"))
      (node (ref "U6") (pin "31") (pinfunction "IO37_31") (pintype "passive"))
    )
    (net (code "28") (name "/SPI_MOSI") (class "Default")
      (node (ref "J4") (pin "2") (pinfunction "2_2") (pintype "passive"))
      (node (ref "U6") (pin "29") (pinfunction "IO35_29") (pintype "passive"))
    )
    (net (code "29") (name "/USB_DM") (class "Default")
      (node (ref "R1") (pin "2") (pinfunction "2_2") (pintype "passive"))
      (node (ref "U3") (pin "4") (pinfunction "D+_4") (pintype "passive"))
    )
    (net (code "30") (name "/USB_DP") (class "Default")
      (node (ref "R3") (pin "2") (pinfunction "2_2") (pintype "passive"))
      (node (ref "U3") (pin "5") (pinfunction "D-_5") (pintype "passive"))
    )
    (net (code "31") (name "GND") (class "Default")
      (node (ref "C12") (pin "1") (pinfunction "1_1") (pintype "passive"))
      (node (ref "C14") (pin "1") (pinfunction "1_1") (pintype "passive"))
      (node (ref "C15") (pin "1") (pinfunction "1_1") (pintype "passive"))
      (node (ref "C16") (pin "1") (pinfunction "1_1") (pintype "passive"))
      (node (ref "C17") (pin "1") (pinfunction "1_1") (pintype "passive"))
      (node (ref "C18") (pin "1") (pinfunction "1_1") (pintype "passive"))
      (node (ref "C19") (pin "1") (pinfunction "1_1") (pintype "passive"))
      (node (ref "C20") (pin "1") (pinfunction "1_1") (pintype "passive"))
      (node (ref "C21") (pin "1") (pinfunction "1_1") (pintype "passive"))
      (node (ref "C22") (pin "2") (pinfunction "2_2") (pintype "passive"))
      (node (ref "C23") (pin "1") (pinfunction "1_1") (pintype "passive"))
      (node (ref "C24") (pin "1") (pinfunction "1_1") (pintype "passive"))
      (node (ref "C25") (pin "1") (pinfunction "1_1") (pintype "passive"))
      (node (ref "C26") (pin "1") (pinfunction "1_1") (pintype "passive"))
      (node (ref "C27") (pin "2") (pinfunction "2_2") (pintype "passive"))
      (node (ref "C28") (pin "2") (pinfunction "2_2") (pintype "passive"))
      (node (ref "C29") (pin "1") (pinfunction "1_1") (pintype "passive"))
      (node (ref "C30") (pin "1") (pinfunction "1_1") (pintype "passive"))
      (node (ref "C31") (pin "1") (pinfunction "1_1") (pintype "passive"))
      (node (ref "C32") (pin "1") (pinfunction "1_1") (pintype "passive"))
      (node (ref "C33") (pin "1") (pinfunction "1_1") (pintype "passive"))
      (node (ref "C34") (pin "1") (pinfunction "1_1") (pintype "passive"))
      (node (ref "C6") (pin "1") (pinfunction "1_1") (pintype "passive"))
      (node (ref "C7") (pin "1") (pinfunction "1_1") (pintype "passive"))
      (node (ref "C8") (pin "1") (pinfunction "1_1") (pintype "passive"))
      (node (ref "C9") (pin "1") (pinfunction "1_1") (pintype "passive"))
      (node (ref "J1") (pin "5") (pinfunction "GND_5") (pintype "passive"))
      (node (ref "J1") (pin "6") (pinfunction "GND1_6") (pintype "passive"))
      (node (ref "J1") (pin "7") (pinfunction "GND2_7") (pintype "passive"))
      (node (ref "J1") (pin "8") (pinfunction "GND3_8") (pintype "passive"))
      (node (ref "J1") (pin "9") (pinfunction "GND4_9") (pintype "passive"))
      (node (ref "J3") (pin "4") (pinfunction "4_4") (pintype "passive"))
      (node (ref "J4") (pin "5") (pinfunction "5_5") (pintype "passive"))
      (node (ref "J7") (pin "2") (pinfunction "2_2") (pintype "passive"))
      (node (ref "Q4") (pin "2") (pinfunction "S_2") (pintype "passive"))
      (node (ref "Q5") (pin "2") (pinfunction "S_2") (pintype "passive"))
      (node (ref "Q6") (pin "2") (pinfunction "S_2") (pintype "passive"))
      (node (ref "Q7") (pin "2") (pinfunction "S_2") (pintype "passive"))
      (node (ref "R10") (pin "1") (pinfunction "1_1") (pintype "passive"))
      (node (ref "R13") (pin "1") (pinfunction "1_1") (pintype "passive"))
      (node (ref "R14") (pin "1") (pinfunction "1_1") (pintype "passive"))
      (node (ref "R19") (pin "1") (pinfunction "1_1") (pintype "passive"))
      (node (ref "R20") (pin "1") (pinfunction "1_1") (pintype "passive"))
      (node (ref "R23") (pin "1") (pinfunction "1_1") (pintype "passive"))
      (node (ref "R24") (pin "1") (pinfunction "1_1") (pintype "passive"))
      (node (ref "R26") (pin "2") (pinfunction "2_2") (pintype "passive"))
      (node (ref "R29") (pin "2") (pinfunction "2_2") (pintype "passive"))
      (node (ref "R30") (pin "2") (pinfunction "2_2") (pintype "passive"))
      (node (ref "R31") (pin "2") (pinfunction "2_2") (pintype "passive"))
      (node (ref "R40") (pin "1") (pinfunction "1_1") (pintype "passive"))
      (node (ref "R42") (pin "1") (pinfunction "1_1") (pintype "passive"))
      (node (ref "R9") (pin "1") (pinfunction "1_1") (pintype "passive"))
      (node (ref "SW1") (pin "4") (pinfunction "4_4") (pintype "passive"))
      (node (ref "SW2") (pin "4") (pinfunction "4_4") (pintype "passive"))
      (node (ref "U1") (pin "2") (pinfunction "GND_2") (pintype "passive"))
      (node (ref "U3") (pin "29") (pinfunction "PGND_29") (pintype "passive"))
      (node (ref "U3") (pin "3") (pinfunction "GND_3") (pintype "passive"))
      (node (ref "U5") (pin "7") (pinfunction "GND_7") (pintype "passive"))
      (node (ref "U5") (pin "9") (pinfunction "PGND_9") (pintype "passive"))
      (node (ref "U6") (pin "1") (pinfunction "GND1_1") (pintype "passive"))
      (node (ref "U6") (pin "26") (pinfunction "GND2_26") (pintype "passive"))
      (node (ref "U6") (pin "42") (pinfunction "GND3_42") (pintype "passive"))
      (node (ref "U6") (pin "43") (pinfunction "EPAD_43") (pintype "passive"))
      (node (ref "U7") (pin "1") (pinfunction "CLKIN_1") (pintype "passive"))
      (node (ref "U7") (pin "11") (pinfunction "FSYNC_11") (pintype "passive"))
      (node (ref "U7") (pin "18") (pinfunction "GND_18") (pintype "passive"))
      (node (ref "U7") (pin "9") (pinfunction "AD0_9") (pintype "passive"))
      (node (ref "U9") (pin "9") (pinfunction "GND_9") (pintype "passive"))
    )
    (net (code "32") (name "Net-(C27-Pad1)") (class "Default")
      (node (ref "C27") (pin "1") (pinfunction "1_1") (pintype "passive"))
      (node (ref "R36") (pin "2") (pinfunction "2_2") (pintype "passive"))
    )
    (net (code "33") (name "Net-(C33-Pad2)") (class "Default")
      (node (ref "C33") (pin "2") (pinfunction "2_2") (pintype "passive"))
      (node (ref "R41") (pin "1") (pinfunction "1_1") (pintype "passive"))
    )
    (net (code "34") (name "Net-(D1-A)") (class "Default")
      (node (ref "D1") (pin "1") (pinfunction "A_1") (pintype "passive"))
      (node (ref "J8") (pin "2") (pinfunction "2_2") (pintype "passive"))
      (node (ref "Q4") (pin "3") (pinfunction "D_3") (pintype "passive"))
    )
    (net (code "35") (name "Net-(D2-A)") (class "Default")
      (node (ref "D2") (pin "1") (pinfunction "A_1") (pintype "passive"))
      (node (ref "J9") (pin "1") (pinfunction "1_1") (pintype "passive"))
      (node (ref "Q5") (pin "3") (pinfunction "D_3") (pintype "passive"))
    )
    (net (code "36") (name "Net-(D4-A)") (class "Default")
      (node (ref "D4") (pin "1") (pinfunction "A_1") (pintype "passive"))
      (node (ref "J5") (pin "2") (pinfunction "2_2") (pintype "passive"))
      (node (ref "Q6") (pin "3") (pinfunction "D_3") (pintype "passive"))
    )
    (net (code "37") (name "Net-(D5-A)") (class "Default")
      (node (ref "D5") (pin "1") (pinfunction "A_1") (pintype "passive"))
      (node (ref "J6") (pin "1") (pinfunction "1_1") (pintype "passive"))
      (node (ref "Q7") (pin "3") (pinfunction "D_3") (pintype "passive"))
    )
    (net (code "38") (name "Net-(D6-Pad2)") (class "Default")
      (node (ref "D6") (pin "2") (pintype "passive"))
      (node (ref "R26") (pin "1") (pinfunction "1_1") (pintype "passive"))
    )
    (net (code "39") (name "Net-(D7-Pad2)") (class "Default")
      (node (ref "D7") (pin "2") (pintype "passive"))
      (node (ref "R29") (pin "1") (pinfunction "1_1") (pintype "passive"))
    )
    (net (code "40") (name "Net-(D8-Pad2)") (class "Default")
      (node (ref "D8") (pin "2") (pintype "passive"))
      (node (ref "R30") (pin "1") (pinfunction "1_1") (pintype "passive"))
    )
    (net (code "41") (name "Net-(D9-Pad2)") (class "Default")
      (node (ref "D9") (pin "2") (pintype "passive"))
      (node (ref "R31") (pin "1") (pinfunction "1_1") (pintype "passive"))
    )
    (net (code "42") (name "Net-(D10-A)") (class "Default")
      (node (ref "D10") (pin "1") (pinfunction "A_1") (pintype "passive"))
      (node (ref "L1") (pin "2") (pinfunction "2_2") (pintype "passive"))
      (node (ref "R36") (pin "1") (pinfunction "1_1") (pintype "passive"))
      (node (ref "U9") (pin "1") (pinfunction "LX_1") (pintype "passive"))
      (node (ref "U9") (pin "2") (pinfunction "LX_2") (pintype "passive"))
    )
    (net (code "43") (name "Net-(J1-D+)") (class "Default")
      (node (ref "J1") (pin "3") (pinfunction "D+_3") (pintype "passive"))
      (node (ref "U1") (pin "3") (pinfunction "IO2_1_3") (pintype "passive"))
    )
    (net (code "44") (name "Net-(J1-D-)") (class "Default")
      (node (ref "J1") (pin "2") (pinfunction "D-_2") (pintype "passive"))
      (node (ref "U1") (pin "1") (pinfunction "IO1_1_1") (pintype "passive"))
    )
    (net (code "45") (name "Net-(R1-Pad1)") (class "Default")
      (node (ref "R1") (pin "1") (pinfunction "1_1") (pintype "passive"))
      (node (ref "U1") (pin "6") (pinfunction "IO2_1_6") (pintype "passive"))
    )
    (net (code "46") (name "Net-(U1-IO2_2)") (class "Default")
      (node (ref "R3") (pin "1") (pinfunction "1_1") (pintype "passive"))
      (node (ref "U1") (pin "4") (pinfunction "IO2_2_4") (pintype "passive"))
    )
    (net (code "47") (name "Net-(U3-RST#)") (class "Default")
      (node (ref "R8") (pin "1") (pinfunction "1_1") (pintype "passive"))
      (node (ref "U3") (pin "9") (pinfunction "RST#_9") (pintype "passive"))
    )
    (net (code "48") (name "Net-(U3-VBUS)") (class "Default")
      (node (ref "R7") (pin "2") (pinfunction "2_2") (pintype "passive"))
      (node (ref "R9") (pin "2") (pinfunction "2_2") (pintype "passive"))
      (node (ref "U3") (pin "8") (pinfunction "VBUS_8") (pintype "passive"))
    )
    (net (code "49") (name "Net-(U5-ADJ)") (class "Default")
      (node (ref "C13") (pin "1") (pinfunction "1_1") (pintype "passive"))
      (node (ref "R18") (pin "1") (pinfunction "1_1") (pintype "passive"))
      (node (ref "R20") (pin "2") (pinfunction "2_2") (pintype "passive"))
      (node (ref "U5") (pin "6") (pinfunction "ADJ_6") (pintype "passive"))
    )
    (net (code "50") (name "Net-(U7-CPOUT)") (class "Default")
      (node (ref "C22") (pin "1") (pinfunction "1_1") (pintype "passive"))
      (node (ref "U7") (pin "20") (pinfunction "CPOUT_20") (pintype "passive"))
    )
    (net (code "51") (name "Net-(U7-REGOUT)") (class "Default")
      (node (ref "C21") (pin "2") (pinfunction "2_2") (pintype "passive"))
      (node (ref "U7") (pin "10") (pinfunction "REGOUT_10") (pintype "passive"))
    )
    (net (code "52") (name "Net-(U8-B1)") (class "Default")
      (node (ref "R34") (pin "2") (pinfunction "2_2") (pintype "passive"))
      (node (ref "U8") (pin "5") (pinfunction "B1_5") (pintype "passive"))
    )
    (net (code "53") (name "Net-(U8-B2)") (class "Default")
      (node (ref "R35") (pin "1") (pinfunction "1_1") (pintype "passive"))
      (node (ref "U8") (pin "2") (pinfunction "B2_2") (pintype "passive"))
    )
    (net (code "54") (name "Net-(U9M-COMP)") (class "Default")
      (node (ref "C34") (pin "2") (pinfunction "2_2") (pintype "passive"))
      (node (ref "R41") (pin "2") (pinfunction "2_2") (pintype "passive"))
      (node (ref "U9") (pin "6") (pinfunction "COMP_6") (pintype "passive"))
    )
    (net (code "55") (name "Net-(U9M-EN)") (class "Default")
      (node (ref "R39") (pin "2") (pinfunction "2_2") (pintype "passive"))
      (node (ref "U9") (pin "4") (pinfunction "EN_4") (pintype "passive"))
    )
    (net (code "56") (name "Net-(U9M-FB)") (class "Default")
      (node (ref "R38") (pin "1") (pinfunction "1_1") (pintype "passive"))
      (node (ref "R42") (pin "2") (pinfunction "2_2") (pintype "passive"))
      (node (ref "U9") (pin "5") (pinfunction "FB_5") (pintype "passive"))
    )
    (net (code "57") (name "Net-(U9M-HVDD)") (class "Default")
      (node (ref "C28") (pin "1") (pinfunction "1_1") (pintype "passive"))
      (node (ref "R37") (pin "1") (pinfunction "1_1") (pintype "passive"))
      (node (ref "U9") (pin "8") (pinfunction "HVDD_8") (pintype "passive"))
    )
    (net (code "58") (name "Net-(U9M-OC)") (class "Default")
      (node (ref "R40") (pin "2") (pinfunction "2_2") (pintype "passive"))
      (node (ref "U9") (pin "7") (pinfunction "OC_7") (pintype "passive"))
    )
    (net (code "59") (name "Net-(U9M-Vcc)") (class "Default")
      (node (ref "C32") (pin "2") (pinfunction "2_2") (pintype "passive"))
      (node (ref "U9") (pin "3") (pinfunction "Vcc_3") (pintype "passive"))
    )
    (net (code "60") (name "VBAT") (class "Default")
      (node (ref "C12") (pin "2") (pinfunction "2_2") (pintype "passive"))
      (node (ref "D1") (pin "2") (pinfunction "K_2") (pintype "passive"))
      (node (ref "D2") (pin "2") (pinfunction "K_2") (pintype "passive"))
      (node (ref "D4") (pin "2") (pinfunction "K_2") (pintype "passive"))
      (node (ref "D5") (pin "2") (pinfunction "K_2") (pintype "passive"))
      (node (ref "J5") (pin "1") (pinfunction "1_1") (pintype "passive"))
      (node (ref "J6") (pin "2") (pinfunction "2_2") (pintype "passive"))
      (node (ref "J7") (pin "1") (pinfunction "1_1") (pintype "passive"))
      (node (ref "J8") (pin "1") (pinfunction "1_1") (pintype "passive"))
      (node (ref "J9") (pin "2") (pinfunction "2_2") (pintype "passive"))
      (node (ref "Q3") (pin "3") (pinfunction "D_3") (pintype "passive"))
      (node (ref "R17") (pin "2") (pinfunction "2_2") (pintype "passive"))
    )
    (net (code "61") (name "VBUS") (class "Default")
      (node (ref "C8") (pin "2") (pinfunction "2_2") (pintype "passive"))
      (node (ref "C9") (pin "2") (pinfunction "2_2") (pintype "passive"))
      (node (ref "D3") (pin "1") (pinfunction "A_1") (pintype "passive"))
      (node (ref "J1") (pin "1") (pinfunction "VBUS_1") (pintype "passive"))
      (node (ref "Q3") (pin "1") (pinfunction "G_1") (pintype "passive"))
      (node (ref "R10") (pin "2") (pinfunction "2_2") (pintype "passive"))
      (node (ref "R7") (pin "1") (pinfunction "1_1") (pintype "passive"))
      (node (ref "U1") (pin "5") (pinfunction "VBUS_5") (pintype "passive"))
      (node (ref "U3") (pin "7") (pinfunction "REGIN_7") (pintype "passive"))
    )
    (net (code "62") (name "VDD33") (class "Default")
      (node (ref "C13") (pin "2") (pinfunction "2_2") (pintype "passive"))
      (node (ref "C15") (pin "2") (pinfunction "2_2") (pintype "passive"))
      (node (ref "C19") (pin "2") (pinfunction "2_2") (pintype "passive"))
      (node (ref "C20") (pin "2") (pinfunction "2_2") (pintype "passive"))
      (node (ref "C25") (pin "2") (pinfunction "2_2") (pintype "passive"))
      (node (ref "C26") (pin "2") (pinfunction "2_2") (pintype "passive"))
      (node (ref "FB1") (pin "1") (pinfunction "1_1") (pintype "passive"))
      (node (ref "J3") (pin "1") (pinfunction "1_1") (pintype "passive"))
      (node (ref "L1") (pin "1") (pinfunction "1_1") (pintype "passive"))
      (node (ref "R18") (pin "2") (pinfunction "2_2") (pintype "passive"))
      (node (ref "R28") (pin "2") (pinfunction "2_2") (pintype "passive"))
      (node (ref "R32") (pin "1") (pinfunction "1_1") (pintype "passive"))
      (node (ref "R33") (pin "1") (pinfunction "1_1") (pintype "passive"))
      (node (ref "R39") (pin "1") (pinfunction "1_1") (pintype "passive"))
      (node (ref "U5") (pin "3") (pinfunction "OUT1_3") (pintype "passive"))
      (node (ref "U5") (pin "4") (pinfunction "OUT2_4") (pintype "passive"))
      (node (ref "U7") (pin "13") (pinfunction "VDD_13") (pintype "passive"))
      (node (ref "U7") (pin "8") (pinfunction "VLOGIO_8") (pintype "passive"))
    )
    (net (code "63") (name "VDD33_ESP") (class "Default")
      (node (ref "C16") (pin "2") (pinfunction "2_2") (pintype "passive"))
      (node (ref "C17") (pin "2") (pinfunction "2_2") (pintype "passive"))
      (node (ref "FB1") (pin "2") (pinfunction "2_2") (pintype "passive"))
      (node (ref "R11") (pin "1") (pinfunction "1_1") (pintype "passive"))
      (node (ref "R12") (pin "1") (pinfunction "1_1") (pintype "passive"))
      (node (ref "R15") (pin "1") (pinfunction "1_1") (pintype "passive"))
      (node (ref "R16") (pin "1") (pinfunction "1_1") (pintype "passive"))
      (node (ref "R21") (pin "2") (pinfunction "2_2") (pintype "passive"))
      (node (ref "R22") (pin "2") (pinfunction "2_2") (pintype "passive"))
      (node (ref "R25") (pin "2") (pinfunction "2_2") (pintype "passive"))
      (node (ref "U6") (pin "2") (pinfunction "VDD33_2") (pintype "passive"))
    )
    (net (code "64") (name "VDD_CP") (class "Default")
      (node (ref "C6") (pin "2") (pinfunction "2_2") (pintype "passive"))
      (node (ref "C7") (pin "2") (pinfunction "2_2") (pintype "passive"))
      (node (ref "R8") (pin "2") (pinfunction "2_2") (pintype "passive"))
      (node (ref "U3") (pin "6") (pinfunction "VDD_6") (pintype "passive"))
    )
    (net (code "65") (name "VSYS") (class "Default")
      (node (ref "C14") (pin "2") (pinfunction "2_2") (pintype "passive"))
      (node (ref "D3") (pin "2") (pinfunction "K_2") (pintype "passive"))
      (node (ref "D6") (pin "1") (pintype "passive"))
      (node (ref "Q3") (pin "2") (pinfunction "S_2") (pintype "passive"))
      (node (ref "U5") (pin "1") (pinfunction "IN_1") (pintype "passive"))
      (node (ref "U5") (pin "2") (pinfunction "IN_2") (pintype "passive"))
      (node (ref "U5") (pin "8") (pinfunction "EN_8") (pintype "passive"))
    )
    (net (code "66") (name "Vout") (class "Default")
      (node (ref "C29") (pin "2") (pinfunction "2_2") (pintype "passive"))
      (node (ref "C30") (pin "2") (pinfunction "2_2") (pintype "passive"))
      (node (ref "C31") (pin "2") (pinfunction "2_2") (pintype "passive"))
      (node (ref "D10") (pin "2") (pinfunction "K_2") (pintype "passive"))
      (node (ref "R37") (pin "2") (pinfunction "2_2") (pintype "passive"))
      (node (ref "R38") (pin "2") (pinfunction "2_2") (pintype "passive"))
    )
    (net (code "67") (name "unconnected-(J1-ID-Pad4)") (class "Default")
      (node (ref "J1") (pin "4") (pinfunction "ID_4") (pintype "passive+no_connect"))
    )
    (net (code "68") (name "unconnected-(J1-MT1-Pad10)") (class "Default")
      (node (ref "J1") (pin "10") (pinfunction "MT1_10") (pintype "passive+no_connect"))
    )
    (net (code "69") (name "unconnected-(J1-MT2-Pad11)") (class "Default")
      (node (ref "J1") (pin "11") (pinfunction "MT2_11") (pintype "passive+no_connect"))
    )
    (net (code "70") (name "unconnected-(SW1-Pad1)") (class "Default")
      (node (ref "SW1") (pin "1") (pinfunction "1_1") (pintype "passive+no_connect"))
    )
    (net (code "71") (name "unconnected-(SW1-Pad3)") (class "Default")
      (node (ref "SW1") (pin "3") (pinfunction "3_3") (pintype "passive+no_connect"))
    )
    (net (code "72") (name "unconnected-(SW2-Pad1)") (class "Default")
      (node (ref "SW2") (pin "1") (pinfunction "1_1") (pintype "passive+no_connect"))
    )
    (net (code "73") (name "unconnected-(SW2-Pad3)") (class "Default")
      (node (ref "SW2") (pin "3") (pinfunction "3_3") (pintype "passive+no_connect"))
    )
    (net (code "74") (name "unconnected-(U3-CTS-Pad23)") (class "Default")
      (node (ref "U3") (pin "23") (pinfunction "CTS_23") (pintype "passive+no_connect"))
    )
    (net (code "75") (name "unconnected-(U3-DCD-Pad1)") (class "Default")
      (node (ref "U3") (pin "1") (pinfunction "DCD_1") (pintype "passive+no_connect"))
    )
    (net (code "76") (name "unconnected-(U3-DSR-Pad27)") (class "Default")
      (node (ref "U3") (pin "27") (pinfunction "DSR_27") (pintype "passive+no_connect"))
    )
    (net (code "77") (name "unconnected-(U3-NC-Pad10)") (class "Default")
      (node (ref "U3") (pin "10") (pinfunction "NC_10") (pintype "passive+no_connect"))
    )
    (net (code "78") (name "unconnected-(U3-NC-Pad13)") (class "Default")
      (node (ref "U3") (pin "13") (pinfunction "NC_13") (pintype "passive+no_connect"))
    )
    (net (code "79") (name "unconnected-(U3-NC-Pad14)") (class "Default")
      (node (ref "U3") (pin "14") (pinfunction "NC_14") (pintype "passive+no_connect"))
    )
    (net (code "80") (name "unconnected-(U3-NC-Pad15)") (class "Default")
      (node (ref "U3") (pin "15") (pinfunction "NC_15") (pintype "passive+no_connect"))
    )
    (net (code "81") (name "unconnected-(U3-NC-Pad16)") (class "Default")
      (node (ref "U3") (pin "16") (pinfunction "NC_16") (pintype "passive+no_connect"))
    )
    (net (code "82") (name "unconnected-(U3-NC-Pad17)") (class "Default")
      (node (ref "U3") (pin "17") (pinfunction "NC_17") (pintype "passive+no_connect"))
    )
    (net (code "83") (name "unconnected-(U3-NC-Pad18)") (class "Default")
      (node (ref "U3") (pin "18") (pinfunction "NC_18") (pintype "passive+no_connect"))
    )
    (net (code "84") (name "unconnected-(U3-NC-Pad19)") (class "Default")
      (node (ref "U3") (pin "19") (pinfunction "NC_19") (pintype "passive+no_connect"))
    )
    (net (code "85") (name "unconnected-(U3-NC-Pad20)") (class "Default")
      (node (ref "U3") (pin "20") (pinfunction "NC_20") (pintype "passive+no_connect"))
    )
    (net (code "86") (name "unconnected-(U3-NC-Pad21)") (class "Default")
      (node (ref "U3") (pin "21") (pinfunction "NC_21") (pintype "passive+no_connect"))
    )
    (net (code "87") (name "unconnected-(U3-NC-Pad22)") (class "Default")
      (node (ref "U3") (pin "22") (pinfunction "NC_22") (pintype "passive+no_connect"))
    )
    (net (code "88") (name "unconnected-(U3-RI-Pad2)") (class "Default")
      (node (ref "U3") (pin "2") (pinfunction "RI_2") (pintype "passive+no_connect"))
    )
    (net (code "89") (name "unconnected-(U3-SUSPEND#-Pad11)") (class "Default")
      (node (ref "U3") (pin "11") (pinfunction "SUSPEND#_11") (pintype "passive+no_connect"))
    )
    (net (code "90") (name "unconnected-(U3-SUSPEND-Pad12)") (class "Default")
      (node (ref "U3") (pin "12") (pinfunction "SUSPEND_12") (pintype "passive+no_connect"))
    )
    (net (code "91") (name "unconnected-(U5-NC-Pad5)") (class "Default")
      (node (ref "U5") (pin "5") (pinfunction "NC_5") (pintype "passive"))
    )
    (net (code "92") (name "unconnected-(U6-IO13-Pad16)") (class "Default")
      (node (ref "U6") (pin "16") (pinfunction "IO13_16") (pintype "passive+no_connect"))
    )
    (net (code "93") (name "unconnected-(U6-IO14-Pad17)") (class "Default")
      (node (ref "U6") (pin "17") (pinfunction "IO14_17") (pintype "passive+no_connect"))
    )
    (net (code "94") (name "unconnected-(U6-IO15-Pad18)") (class "Default")
      (node (ref "U6") (pin "18") (pinfunction "IO15_18") (pintype "passive+no_connect"))
    )
    (net (code "95") (name "unconnected-(U6-IO16-Pad19)") (class "Default")
      (node (ref "U6") (pin "19") (pinfunction "IO16_19") (pintype "passive+no_connect"))
    )
    (net (code "96") (name "unconnected-(U6-IO17-Pad20)") (class "Default")
      (node (ref "U6") (pin "20") (pinfunction "IO17_20") (pintype "passive+no_connect"))
    )
    (net (code "97") (name "unconnected-(U6-IO18-Pad21)") (class "Default")
      (node (ref "U6") (pin "21") (pinfunction "IO18_21") (pintype "passive+no_connect"))
    )
    (net (code "98") (name "unconnected-(U6-IO19-Pad22)") (class "Default")
      (node (ref "U6") (pin "22") (pinfunction "IO19_22") (pintype "passive+no_connect"))
    )
    (net (code "99") (name "unconnected-(U6-IO20-Pad23)") (class "Default")
      (node (ref "U6") (pin "23") (pinfunction "IO20_23") (pintype "passive+no_connect"))
    )
    (net (code "100") (name "unconnected-(U6-IO21-Pad24)") (class "Default")
      (node (ref "U6") (pin "24") (pinfunction "IO21_24") (pintype "passive+no_connect"))
    )
    (net (code "101") (name "unconnected-(U6-IO26-Pad25)") (class "Default")
      (node (ref "U6") (pin "25") (pinfunction "IO26_25") (pintype "passive+no_connect"))
    )
    (net (code "102") (name "unconnected-(U6-IO33-Pad27)") (class "Default")
      (node (ref "U6") (pin "27") (pinfunction "IO33_27") (pintype "passive+no_connect"))
    )
    (net (code "103") (name "unconnected-(U6-IO42-Pad36)") (class "Default")
      (node (ref "U6") (pin "36") (pinfunction "IO42_36") (pintype "passive+no_connect"))
    )
    (net (code "104") (name "unconnected-(U6-IO45-Pad39)") (class "Default")
      (node (ref "U6") (pin "39") (pinfunction "IO45_39") (pintype "passive+no_connect"))
    )
    (net (code "105") (name "unconnected-(U6-IO46-Pad40)") (class "Default")
      (node (ref "U6") (pin "40") (pinfunction "IO46_40") (pintype "passive+no_connect"))
    )
    (net (code "106") (name "unconnected-(U7-NC-Pad2)") (class "Default")
      (node (ref "U7") (pin "2") (pinfunction "NC_2") (pintype "passive+no_connect"))
    )
    (net (code "107") (name "unconnected-(U7-NC-Pad3)") (class "Default")
      (node (ref "U7") (pin "3") (pinfunction "NC_3") (pintype "passive+no_connect"))
    )
    (net (code "108") (name "unconnected-(U7-NC-Pad4)") (class "Default")
      (node (ref "U7") (pin "4") (pinfunction "NC_4") (pintype "passive+no_connect"))
    )
    (net (code "109") (name "unconnected-(U7-NC-Pad5)") (class "Default")
      (node (ref "U7") (pin "5") (pinfunction "NC_5") (pintype "passive+no_connect"))
    )
    (net (code "110") (name "unconnected-(U7-NC-Pad14)") (class "Default")
      (node (ref "U7") (pin "14") (pinfunction "NC_14") (pintype "passive+no_connect"))
    )
    (net (code "111") (name "unconnected-(U7-NC-Pad15)") (class "Default")
      (node (ref "U7") (pin "15") (pinfunction "NC_15") (pintype "passive+no_connect"))
    )
    (net (code "112") (name "unconnected-(U7-NC-Pad16)") (class "Default")
      (node (ref "U7") (pin "16") (pinfunction "NC_16") (pintype "passive+no_connect"))
    )
    (net (code "113") (name "unconnected-(U7-NC-Pad17)") (class "Default")
      (node (ref "U7") (pin "17") (pinfunction "NC_17") (pintype "passive+no_connect"))
    )
    (net (code "114") (name "unconnected-(U7-RESV-Pad19)") (class "Default")
      (node (ref "U7") (pin "19") (pinfunction "RESV_19") (pintype "passive+no_connect"))
    )
    (net (code "115") (name "unconnected-(U7-RESV-Pad21)") (class "Default")
      (node (ref "U7") (pin "21") (pinfunction "RESV_21") (pintype "passive+no_connect"))
    )
    (net (code "116") (name "unconnected-(U7-RESV-Pad22)") (class "Default")
      (node (ref "U7") (pin "22") (pinfunction "RESV_22") (pintype "passive+no_connect"))
    )
  )
)
